# PCB1.net
KiCad netlist of a schematic drawn in Altium Designer
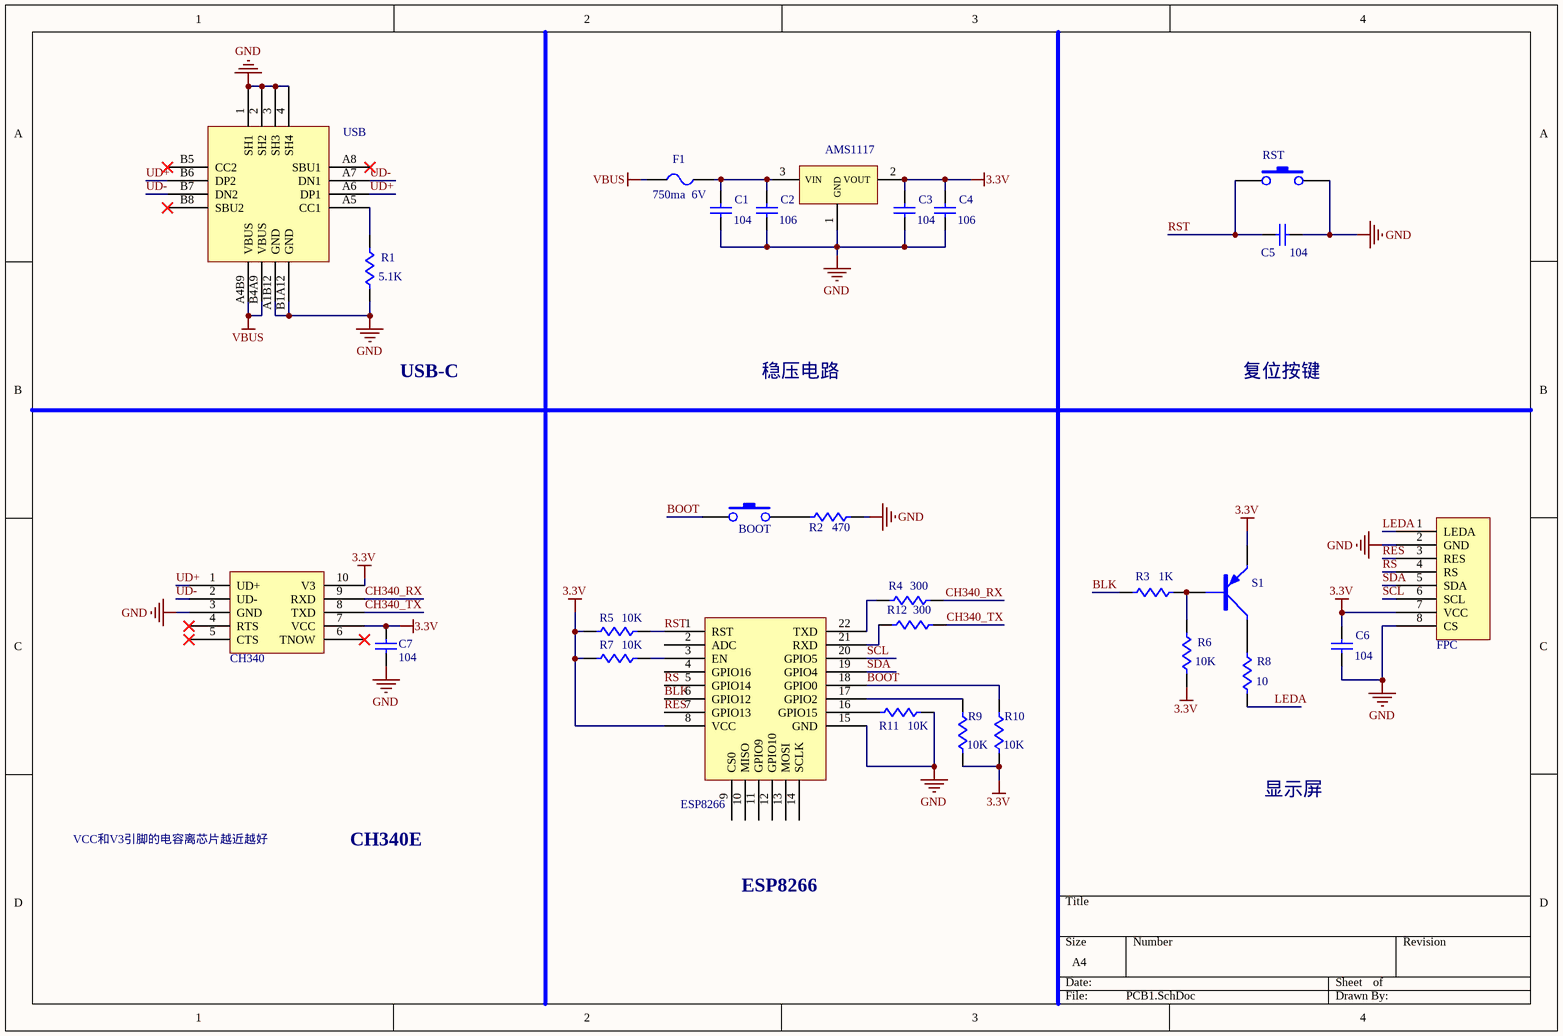
[diagram p0: PCB1.SchDoc]

(export (version "E")
  (design (tool "Eeschema 10.0.6"))
  (components
    (comp (ref "AMS1117")
      (value "AMS-3V3")
      (footprint "SOT89-M")
      (libsource (lib "Integrated_Library1") (part "AMS-3V3"))
    )
    (comp (ref "BOOT")
      (value "KEY3*4mm")
      (footprint "KEY3*4mm")
      (libsource (lib "Integrated_Library1") (part "KEY3*4mm"))
    )
    (comp (ref "C1")
      (value "104")
      (footprint "0603-C")
      (description "电容-0603")
      (fields (field (name "Comment") "CAP"))
      (libsource (lib "Integrated_Library1") (part "CAP"))
    )
    (comp (ref "C2")
      (value "106")
      (footprint "0603-C")
      (description "电容-0603")
      (fields (field (name "Comment") "CAP"))
      (libsource (lib "Integrated_Library1") (part "CAP"))
    )
    (comp (ref "C3")
      (value "104")
      (footprint "0603-C")
      (description "电容-0603")
      (fields (field (name "Comment") "CAP"))
      (libsource (lib "Integrated_Library1") (part "CAP"))
    )
    (comp (ref "C4")
      (value "106")
      (footprint "0603-C")
      (description "电容-0603")
      (fields (field (name "Comment") "CAP"))
      (libsource (lib "Integrated_Library1") (part "CAP"))
    )
    (comp (ref "C5")
      (value "104")
      (footprint "0603-C")
      (description "电容-0603")
      (fields (field (name "Comment") "CAP"))
      (libsource (lib "Integrated_Library1") (part "CAP"))
    )
    (comp (ref "C6")
      (value "104")
      (footprint "0603-C")
      (description "电容-0603")
      (fields (field (name "Comment") "CAP"))
      (libsource (lib "Integrated_Library1") (part "CAP"))
    )
    (comp (ref "C7")
      (value "104")
      (footprint "0603-C")
      (description "电容-0603")
      (fields (field (name "Comment") "CAP"))
      (libsource (lib "Integrated_Library1") (part "CAP"))
    )
    (comp (ref "CH340") (value "CH340E") (footprint "CH340E") (libsource (lib "Schlib1") (part "CH340E")))
    (comp (ref "ESP8266")
      (value "ESP8266-12F")
      (footprint "ESP8266-12F")
      (libsource (lib "Schlib1") (part "ESP8266-12F"))
    )
    (comp (ref "F1")
      (value "750ma  6V")
      (footprint "PTC-0603")
      (description "贴片保险丝")
      (libsource (lib "Integrated_Library1") (part "FU"))
    )
    (comp (ref "FPC")
      (value "FPC Connector")
      (footprint "FPC Connector")
      (libsource (lib "Schlib1") (part "FPC Connector"))
    )
    (comp (ref "R1")
      (value "5.1K")
      (footprint "0603-R")
      (description "电阻-0603")
      (fields (field (name "Comment") "RES"))
      (libsource (lib "Integrated_Library1") (part "RES"))
    )
    (comp (ref "R2")
      (value "470")
      (footprint "0603-R")
      (description "电阻-0603")
      (fields (field (name "Comment") "RES"))
      (libsource (lib "Integrated_Library1") (part "RES"))
    )
    (comp (ref "R3")
      (value "1K")
      (footprint "0603-R")
      (description "电阻-0603")
      (fields (field (name "Comment") "RES"))
      (libsource (lib "Integrated_Library1") (part "RES"))
    )
    (comp (ref "R4")
      (value "300")
      (footprint "0603-R")
      (description "电阻-0603")
      (fields (field (name "Comment") "RES"))
      (libsource (lib "Integrated_Library1") (part "RES"))
    )
    (comp (ref "R5")
      (value "10K")
      (footprint "0603-R")
      (description "电阻-0603")
      (fields (field (name "Comment") "RES"))
      (libsource (lib "Integrated_Library1") (part "RES"))
    )
    (comp (ref "R6")
      (value "10K")
      (footprint "0603-R")
      (description "电阻-0603")
      (fields (field (name "Comment") "RES"))
      (libsource (lib "Integrated_Library1") (part "RES"))
    )
    (comp (ref "R7")
      (value "10K")
      (footprint "0603-R")
      (description "电阻-0603")
      (fields (field (name "Comment") "RES"))
      (libsource (lib "Integrated_Library1") (part "RES"))
    )
    (comp (ref "R8")
      (value "10")
      (footprint "0603-R")
      (description "电阻-0603")
      (fields (field (name "Comment") "RES"))
      (libsource (lib "Integrated_Library1") (part "RES"))
    )
    (comp (ref "R9")
      (value "10K")
      (footprint "0603-R")
      (description "电阻-0603")
      (fields (field (name "Comment") "RES"))
      (libsource (lib "Integrated_Library1") (part "RES"))
    )
    (comp (ref "R10")
      (value "10K")
      (footprint "0603-R")
      (description "电阻-0603")
      (fields (field (name "Comment") "RES"))
      (libsource (lib "Integrated_Library1") (part "RES"))
    )
    (comp (ref "R11")
      (value "10K")
      (footprint "0603-R")
      (description "电阻-0603")
      (fields (field (name "Comment") "RES"))
      (libsource (lib "Integrated_Library1") (part "RES"))
    )
    (comp (ref "R12")
      (value "300")
      (footprint "0603-R")
      (description "电阻-0603")
      (fields (field (name "Comment") "RES"))
      (libsource (lib "Integrated_Library1") (part "RES"))
    )
    (comp (ref "RST")
      (value "KEY3*4mm")
      (footprint "KEY3*4mm")
      (libsource (lib "Integrated_Library1") (part "KEY3*4mm"))
    )
    (comp (ref "S1")
      (value "S8550")
      (footprint "S8550")
      (libsource (lib "Integrated_Library1") (part "S8550"))
    )
    (comp (ref "USB") (value "TYPE-C") (footprint "TYPE-C") (libsource (lib "Schlib1") (part "TYPE-C")))
  )
  (nets
    (net (code "1") (name "/BLK") (class "Default")
      (node (ref "ESP8266") (pin "6") (pinfunction "GPIO12_6") (pintype "passive"))
      (node (ref "R3") (pin "2") (pinfunction "2_2") (pintype "passive"))
    )
    (net (code "2") (name "/BOOT") (class "Default")
      (node (ref "BOOT") (pin "1") (pinfunction "1_1") (pintype "passive"))
      (node (ref "ESP8266") (pin "18") (pinfunction "GPIO0_18") (pintype "passive"))
      (node (ref "R10") (pin "1") (pinfunction "1_1") (pintype "passive"))
    )
    (net (code "3") (name "/CH340_RX") (class "Default")
      (node (ref "CH340") (pin "9") (pinfunction "RXD_9") (pintype "passive"))
      (node (ref "R4") (pin "1") (pinfunction "1_1") (pintype "passive"))
    )
    (net (code "4") (name "/CH340_TX") (class "Default")
      (node (ref "CH340") (pin "8") (pinfunction "TXD_8") (pintype "passive"))
      (node (ref "R12") (pin "1") (pinfunction "1_1") (pintype "passive"))
    )
    (net (code "5") (name "/LEDA") (class "Default")
      (node (ref "FPC") (pin "1") (pinfunction "LEDA_1") (pintype "passive"))
      (node (ref "R8") (pin "1") (pinfunction "1_1") (pintype "passive"))
    )
    (net (code "6") (name "/RES") (class "Default")
      (node (ref "ESP8266") (pin "7") (pinfunction "GPIO13_7") (pintype "passive"))
      (node (ref "FPC") (pin "3") (pinfunction "RES_3") (pintype "passive"))
    )
    (net (code "7") (name "/RS") (class "Default")
      (node (ref "ESP8266") (pin "5") (pinfunction "GPIO14_5") (pintype "passive"))
      (node (ref "FPC") (pin "4") (pinfunction "RS_4") (pintype "passive"))
    )
    (net (code "8") (name "/RST") (class "Default")
      (node (ref "C5") (pin "2") (pinfunction "2_2") (pintype "passive"))
      (node (ref "ESP8266") (pin "1") (pinfunction "RST_1") (pintype "passive"))
      (node (ref "R5") (pin "1") (pinfunction "1_1") (pintype "passive"))
      (node (ref "RST") (pin "1") (pinfunction "1_1") (pintype "passive"))
    )
    (net (code "9") (name "/SCL") (class "Default")
      (node (ref "ESP8266") (pin "20") (pinfunction "GPIO5_20") (pintype "passive"))
      (node (ref "FPC") (pin "6") (pinfunction "SCL_6") (pintype "passive"))
    )
    (net (code "10") (name "/SDA") (class "Default")
      (node (ref "ESP8266") (pin "19") (pinfunction "GPIO4_19") (pintype "passive"))
      (node (ref "FPC") (pin "5") (pinfunction "SDA_5") (pintype "passive"))
    )
    (net (code "11") (name "/UD+") (class "Default")
      (node (ref "CH340") (pin "1") (pinfunction "UD+_1") (pintype "passive"))
      (node (ref "USB") (pin "A6") (pinfunction "DP1_A6") (pintype "passive"))
      (node (ref "USB") (pin "B6") (pinfunction "DP2_B6") (pintype "passive"))
    )
    (net (code "12") (name "/UD-") (class "Default")
      (node (ref "CH340") (pin "2") (pinfunction "UD-_2") (pintype "passive"))
      (node (ref "USB") (pin "A7") (pinfunction "DN1_A7") (pintype "passive"))
      (node (ref "USB") (pin "B7") (pinfunction "DN2_B7") (pintype "passive"))
    )
    (net (code "13") (name "3.3V") (class "Default")
      (node (ref "AMS1117") (pin "2") (pinfunction "VOUT_2") (pintype "passive"))
      (node (ref "C3") (pin "2") (pinfunction "2_2") (pintype "passive"))
      (node (ref "C4") (pin "2") (pinfunction "2_2") (pintype "passive"))
      (node (ref "C6") (pin "2") (pinfunction "2_2") (pintype "passive"))
      (node (ref "C7") (pin "1") (pinfunction "1_1") (pintype "passive"))
      (node (ref "CH340") (pin "10") (pinfunction "V3_10") (pintype "passive"))
      (node (ref "CH340") (pin "7") (pinfunction "VCC_7") (pintype "passive"))
      (node (ref "ESP8266") (pin "8") (pinfunction "VCC_8") (pintype "passive"))
      (node (ref "FPC") (pin "7") (pinfunction "VCC_7") (pintype "passive"))
      (node (ref "R10") (pin "2") (pinfunction "2_2") (pintype "passive"))
      (node (ref "R5") (pin "2") (pinfunction "2_2") (pintype "passive"))
      (node (ref "R6") (pin "1") (pinfunction "1_1") (pintype "passive"))
      (node (ref "R7") (pin "2") (pinfunction "2_2") (pintype "passive"))
      (node (ref "R9") (pin "1") (pinfunction "1_1") (pintype "passive"))
      (node (ref "S1") (pin "2") (pinfunction "E_2") (pintype "passive"))
    )
    (net (code "14") (name "GND") (class "Default")
      (node (ref "AMS1117") (pin "1") (pinfunction "GND_1") (pintype "passive"))
      (node (ref "C1") (pin "1") (pinfunction "1_1") (pintype "passive"))
      (node (ref "C2") (pin "1") (pinfunction "1_1") (pintype "passive"))
      (node (ref "C3") (pin "1") (pinfunction "1_1") (pintype "passive"))
      (node (ref "C4") (pin "1") (pinfunction "1_1") (pintype "passive"))
      (node (ref "C5") (pin "1") (pinfunction "1_1") (pintype "passive"))
      (node (ref "C6") (pin "1") (pinfunction "1_1") (pintype "passive"))
      (node (ref "C7") (pin "2") (pinfunction "2_2") (pintype "passive"))
      (node (ref "CH340") (pin "3") (pinfunction "GND_3") (pintype "passive"))
      (node (ref "ESP8266") (pin "15") (pinfunction "GND_15") (pintype "passive"))
      (node (ref "FPC") (pin "2") (pinfunction "GND_2") (pintype "passive"))
      (node (ref "FPC") (pin "8") (pinfunction "CS_8") (pintype "passive"))
      (node (ref "R1") (pin "1") (pinfunction "1_1") (pintype "passive"))
      (node (ref "R11") (pin "1") (pinfunction "1_1") (pintype "passive"))
      (node (ref "R2") (pin "2") (pinfunction "2_2") (pintype "passive"))
      (node (ref "RST") (pin "2") (pinfunction "2_2") (pintype "passive"))
      (node (ref "USB") (pin "1") (pinfunction "SH1_1") (pintype "passive"))
      (node (ref "USB") (pin "2") (pinfunction "SH2_2") (pintype "passive"))
      (node (ref "USB") (pin "3") (pinfunction "SH3_3") (pintype "passive"))
      (node (ref "USB") (pin "4") (pinfunction "SH4_4") (pintype "passive"))
      (node (ref "USB") (pin "A1B12") (pinfunction "GND_A1B12") (pintype "passive"))
      (node (ref "USB") (pin "B1A12") (pinfunction "GND_B1A12") (pintype "passive"))
    )
    (net (code "15") (name "Net-(AMS1117-VIN)") (class "Default")
      (node (ref "AMS1117") (pin "3") (pinfunction "VIN_3") (pintype "passive"))
      (node (ref "C1") (pin "2") (pinfunction "2_2") (pintype "passive"))
      (node (ref "C2") (pin "2") (pinfunction "2_2") (pintype "passive"))
      (node (ref "F1") (pin "2") (pinfunction "2_2") (pintype "passive"))
    )
    (net (code "16") (name "Net-(BOOT-Pad2)") (class "Default")
      (node (ref "BOOT") (pin "2") (pinfunction "2_2") (pintype "passive"))
      (node (ref "R2") (pin "1") (pinfunction "1_1") (pintype "passive"))
    )
    (net (code "17") (name "Net-(ESP8266-EN)") (class "Default")
      (node (ref "ESP8266") (pin "3") (pinfunction "EN_3") (pintype "passive"))
      (node (ref "R7") (pin "1") (pinfunction "1_1") (pintype "passive"))
    )
    (net (code "18") (name "Net-(ESP8266-GPIO2)") (class "Default")
      (node (ref "ESP8266") (pin "17") (pinfunction "GPIO2_17") (pintype "passive"))
      (node (ref "R9") (pin "2") (pinfunction "2_2") (pintype "passive"))
    )
    (net (code "19") (name "Net-(ESP8266-GPIO15)") (class "Default")
      (node (ref "ESP8266") (pin "16") (pinfunction "GPIO15_16") (pintype "passive"))
      (node (ref "R11") (pin "2") (pinfunction "2_2") (pintype "passive"))
    )
    (net (code "20") (name "Net-(ESP8266-RXD)") (class "Default")
      (node (ref "ESP8266") (pin "21") (pinfunction "RXD_21") (pintype "passive"))
      (node (ref "R12") (pin "2") (pinfunction "2_2") (pintype "passive"))
    )
    (net (code "21") (name "Net-(ESP8266-TXD)") (class "Default")
      (node (ref "ESP8266") (pin "22") (pinfunction "TXD_22") (pintype "passive"))
      (node (ref "R4") (pin "2") (pinfunction "2_2") (pintype "passive"))
    )
    (net (code "22") (name "Net-(S1-B)") (class "Default")
      (node (ref "R3") (pin "1") (pinfunction "1_1") (pintype "passive"))
      (node (ref "R6") (pin "2") (pinfunction "2_2") (pintype "passive"))
      (node (ref "S1") (pin "1") (pinfunction "B_1") (pintype "passive"))
    )
    (net (code "23") (name "Net-(S1-C)") (class "Default")
      (node (ref "R8") (pin "2") (pinfunction "2_2") (pintype "passive"))
      (node (ref "S1") (pin "3") (pinfunction "C_3") (pintype "passive"))
    )
    (net (code "24") (name "Net-(USB-CC1)") (class "Default")
      (node (ref "R1") (pin "2") (pinfunction "2_2") (pintype "passive"))
      (node (ref "USB") (pin "A5") (pinfunction "CC1_A5") (pintype "passive"))
    )
    (net (code "25") (name "VBUS") (class "Default")
      (node (ref "F1") (pin "1") (pinfunction "1_1") (pintype "passive"))
      (node (ref "USB") (pin "A4B9") (pinfunction "VBUS_A4B9") (pintype "passive"))
      (node (ref "USB") (pin "B4A9") (pinfunction "VBUS_B4A9") (pintype "passive"))
    )
    (net (code "26") (name "unconnected-(CH340-CTS-Pad5)") (class "Default")
      (node (ref "CH340") (pin "5") (pinfunction "CTS_5") (pintype "passive+no_connect"))
    )
    (net (code "27") (name "unconnected-(CH340-RTS-Pad4)") (class "Default")
      (node (ref "CH340") (pin "4") (pinfunction "RTS_4") (pintype "passive+no_connect"))
    )
    (net (code "28") (name "unconnected-(CH340-TNOW-Pad6)") (class "Default")
      (node (ref "CH340") (pin "6") (pinfunction "TNOW_6") (pintype "passive+no_connect"))
    )
    (net (code "29") (name "unconnected-(ESP8266-ADC-Pad2)") (class "Default")
      (node (ref "ESP8266") (pin "2") (pinfunction "ADC_2") (pintype "passive"))
    )
    (net (code "30") (name "unconnected-(ESP8266-CS0-Pad9)") (class "Default")
      (node (ref "ESP8266") (pin "9") (pinfunction "CS0_9") (pintype "passive"))
    )
    (net (code "31") (name "unconnected-(ESP8266-GPIO9-Pad11)") (class "Default")
      (node (ref "ESP8266") (pin "11") (pinfunction "GPIO9_11") (pintype "passive"))
    )
    (net (code "32") (name "unconnected-(ESP8266-GPIO10-Pad12)") (class "Default")
      (node (ref "ESP8266") (pin "12") (pinfunction "GPIO10_12") (pintype "passive"))
    )
    (net (code "33") (name "unconnected-(ESP8266-GPIO16-Pad4)") (class "Default")
      (node (ref "ESP8266") (pin "4") (pinfunction "GPIO16_4") (pintype "passive"))
    )
    (net (code "34") (name "unconnected-(ESP8266-MISO-Pad10)") (class "Default")
      (node (ref "ESP8266") (pin "10") (pinfunction "MISO_10") (pintype "passive"))
    )
    (net (code "35") (name "unconnected-(ESP8266-MOSI-Pad13)") (class "Default")
      (node (ref "ESP8266") (pin "13") (pinfunction "MOSI_13") (pintype "passive"))
    )
    (net (code "36") (name "unconnected-(ESP8266-SCLK-Pad14)") (class "Default")
      (node (ref "ESP8266") (pin "14") (pinfunction "SCLK_14") (pintype "passive"))
    )
    (net (code "37") (name "unconnected-(USB-CC2-PadB5)") (class "Default")
      (node (ref "USB") (pin "B5") (pinfunction "CC2_B5") (pintype "passive+no_connect"))
    )
    (net (code "38") (name "unconnected-(USB-SBU1-PadA8)") (class "Default")
      (node (ref "USB") (pin "A8") (pinfunction "SBU1_A8") (pintype "passive+no_connect"))
    )
    (net (code "39") (name "unconnected-(USB-SBU2-PadB8)") (class "Default")
      (node (ref "USB") (pin "B8") (pinfunction "SBU2_B8") (pintype "passive+no_connect"))
    )
  )
)
